# Controller.net
KiCad netlist of a schematic drawn in EAGLE
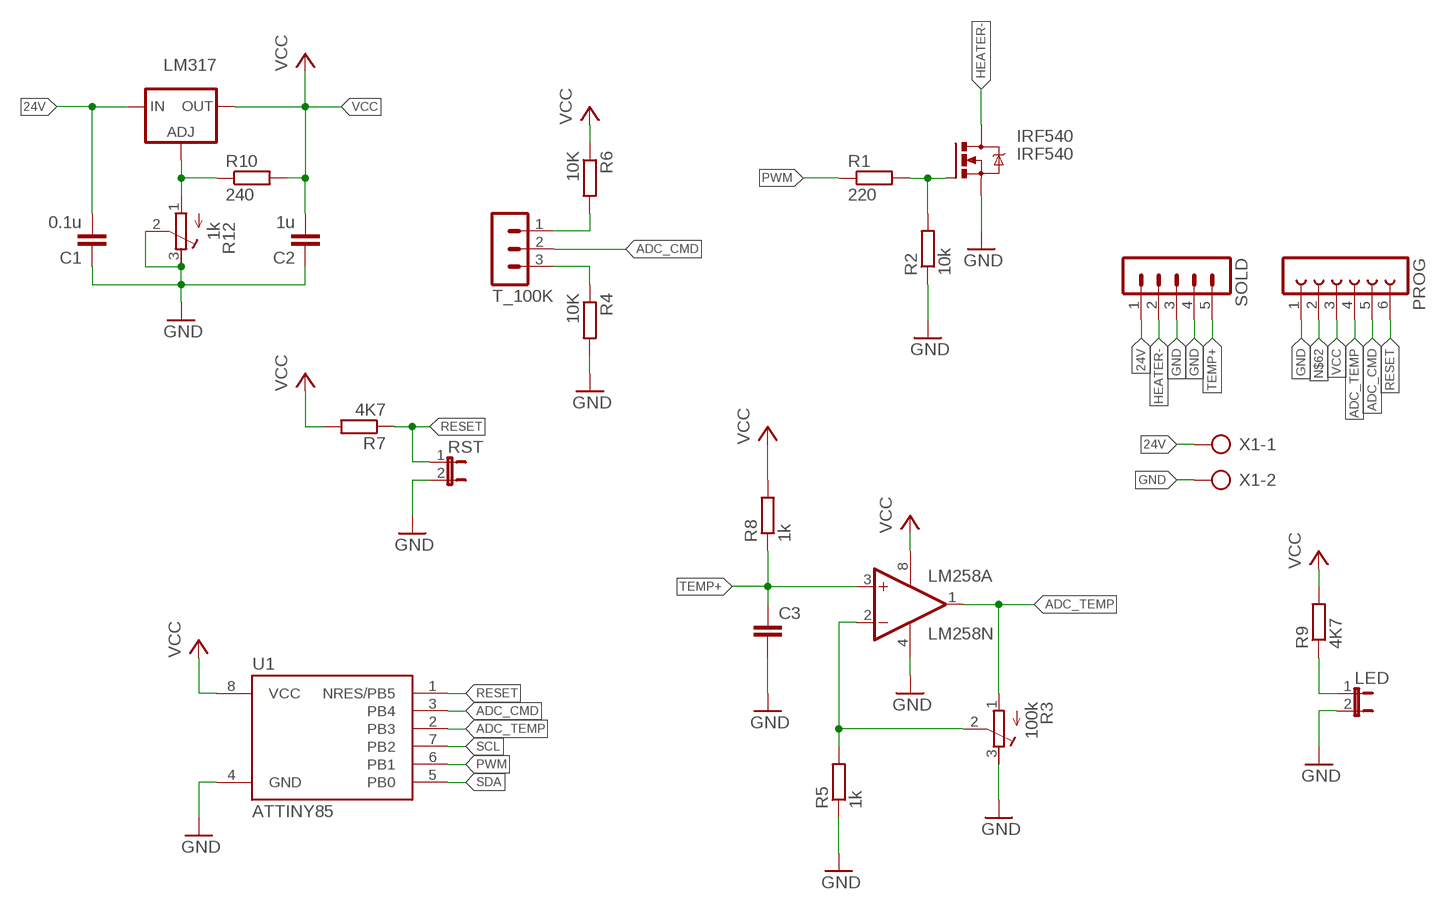
[diagram p0: schematic, sheet 1]

(export (version "E")
  (design (tool "Eeschema 10.0.6"))
  (components
    (comp (ref "C1")
      (value "0.1u")
      (footprint "eagle-import:C025-025X050")
      (libsource (lib "eagle-import") (part "C-EU025-025X050"))
    )
    (comp (ref "C2")
      (value "1u")
      (footprint "eagle-import:C025-025X050")
      (libsource (lib "eagle-import") (part "C-EU025-025X050"))
    )
    (comp (ref "C3")
      (value "C-EU025-025X050")
      (footprint "eagle-import:C025-025X050")
      (libsource (lib "eagle-import") (part "C-EU025-025X050"))
    )
    (comp (ref "IRF540")
      (value "IRF540")
      (footprint "eagle-import:TO220BV")
      (libsource (lib "eagle-import") (part "IRF540"))
    )
    (comp (ref "LED")
      (value "JP1E")
      (footprint "eagle-import:JP1")
      (libsource (lib "eagle-import") (part "JP1E"))
    )
    (comp (ref "LM258")
      (value "LM258N")
      (footprint "eagle-import:DIL08")
      (libsource (lib "eagle-import") (part "LM2903N"))
    )
    (comp (ref "LM317")
      (value "LM317TS")
      (footprint "eagle-import:317TS")
      (libsource (lib "eagle-import") (part "LM317TS"))
    )
    (comp (ref "PROG")
      (value "FE06-1")
      (footprint "eagle-import:FE06")
      (libsource (lib "eagle-import") (part "FE06-1"))
    )
    (comp (ref "R1")
      (value "220")
      (footprint "eagle-import:0204_7")
      (libsource (lib "eagle-import") (part "R-EU_0204/7"))
    )
    (comp (ref "R2")
      (value "10k")
      (footprint "eagle-import:0204_7")
      (libsource (lib "eagle-import") (part "R-EU_0204/7"))
    )
    (comp (ref "R3")
      (value "100k")
      (footprint "eagle-import:RTRIM64W")
      (libsource (lib "eagle-import") (part "R-TRIMM64W"))
    )
    (comp (ref "R4")
      (value "10K")
      (footprint "eagle-import:0204V")
      (libsource (lib "eagle-import") (part "R-EU_0204/2V"))
    )
    (comp (ref "R5")
      (value "1k")
      (footprint "eagle-import:0204_7")
      (libsource (lib "eagle-import") (part "R-EU_0204/7"))
    )
    (comp (ref "R6")
      (value "10K")
      (footprint "eagle-import:0204_7")
      (libsource (lib "eagle-import") (part "R-EU_0204/7"))
    )
    (comp (ref "R7")
      (value "4K7")
      (footprint "eagle-import:0204_7")
      (libsource (lib "eagle-import") (part "R-EU_0204/7"))
    )
    (comp (ref "R8")
      (value "1k")
      (footprint "eagle-import:0204_7")
      (libsource (lib "eagle-import") (part "R-EU_0204/7"))
    )
    (comp (ref "R9")
      (value "4K7")
      (footprint "eagle-import:0204_7")
      (libsource (lib "eagle-import") (part "R-EU_0204/7"))
    )
    (comp (ref "R10")
      (value "240")
      (footprint "eagle-import:0204_7")
      (libsource (lib "eagle-import") (part "R-EU_0204/7"))
    )
    (comp (ref "R12")
      (value "1k")
      (footprint "eagle-import:RTRIM64W")
      (libsource (lib "eagle-import") (part "R-TRIMM64W"))
    )
    (comp (ref "RST")
      (value "JP1E")
      (footprint "eagle-import:JP1")
      (libsource (lib "eagle-import") (part "JP1E"))
    )
    (comp (ref "SOLD")
      (value "MA05-1")
      (footprint "eagle-import:MA05-1")
      (libsource (lib "eagle-import") (part "MA05-1"))
    )
    (comp (ref "T_100K")
      (value "MA03-1")
      (footprint "eagle-import:MA03-1")
      (libsource (lib "eagle-import") (part "MA03-1"))
    )
    (comp (ref "U1")
      (value "ATTINY85")
      (footprint "eagle-import:PDIP08_300MIL")
      (libsource (lib "eagle-import") (part "ATTINY85P-"))
    )
    (comp (ref "X1")
      (value "SMKDSP_1,5/2")
      (footprint "eagle-import:SMKDSP_1,5_2")
      (fields (field (name "MF") "FARNELL") (field (name "MPN") "1733570"))
      (libsource (lib "eagle-import") (part "SMKDSP_1,5/2"))
    )
  )
  (nets
    (net (code "1") (name "24V") (class "Default")
      (node (ref "C1") (pin "2") (pinfunction "2_2") (pintype "passive"))
      (node (ref "LM317") (pin "3") (pinfunction "IN_3") (pintype "input"))
      (node (ref "SOLD") (pin "1") (pinfunction "1_1") (pintype "passive"))
      (node (ref "X1") (pin "1") (pinfunction "KL_1") (pintype "passive"))
    )
    (net (code "2") (name "ADC_CMD") (class "Default")
      (node (ref "PROG") (pin "5") (pinfunction "5_5") (pintype "passive"))
      (node (ref "R6") (pin "2") (pinfunction "2_2") (pintype "passive"))
      (node (ref "T_100K") (pin "1") (pinfunction "1_1") (pintype "passive"))
      (node (ref "T_100K") (pin "2") (pinfunction "2_2") (pintype "passive"))
      (node (ref "U1") (pin "3") (pinfunction "PB4_3") (pintype "bidirectional"))
    )
    (net (code "3") (name "ADC_TEMP") (class "Default")
      (node (ref "LM258") (pin "1") (pinfunction "OUT_1") (pintype "output"))
      (node (ref "PROG") (pin "4") (pinfunction "4_4") (pintype "passive"))
      (node (ref "R3") (pin "1") (pinfunction "A_1") (pintype "passive"))
      (node (ref "U1") (pin "2") (pinfunction "PB3_2") (pintype "bidirectional"))
    )
    (net (code "4") (name "GND") (class "Default")
      (node (ref "C1") (pin "1") (pinfunction "1_1") (pintype "passive"))
      (node (ref "C2") (pin "1") (pinfunction "1_1") (pintype "passive"))
      (node (ref "C3") (pin "2") (pinfunction "2_2") (pintype "passive"))
      (node (ref "IRF540") (pin "S") (pinfunction "S_S") (pintype "passive"))
      (node (ref "LED") (pin "2") (pinfunction "2_2") (pintype "passive"))
      (node (ref "LM258") (pin "4") (pinfunction "V-_4") (pintype "power_in"))
      (node (ref "PROG") (pin "1") (pinfunction "1_1") (pintype "passive"))
      (node (ref "R12") (pin "2") (pinfunction "S_2") (pintype "passive"))
      (node (ref "R12") (pin "3") (pinfunction "E_3") (pintype "passive"))
      (node (ref "R2") (pin "1") (pinfunction "1_1") (pintype "passive"))
      (node (ref "R3") (pin "3") (pinfunction "E_3") (pintype "passive"))
      (node (ref "R4") (pin "2") (pinfunction "2_2") (pintype "passive"))
      (node (ref "R5") (pin "1") (pinfunction "1_1") (pintype "passive"))
      (node (ref "RST") (pin "2") (pinfunction "2_2") (pintype "passive"))
      (node (ref "SOLD") (pin "3") (pinfunction "3_3") (pintype "passive"))
      (node (ref "SOLD") (pin "4") (pinfunction "4_4") (pintype "passive"))
      (node (ref "U1") (pin "4") (pinfunction "GND_4") (pintype "power_in"))
      (node (ref "X1") (pin "2") (pinfunction "KL_2") (pintype "passive"))
    )
    (net (code "5") (name "HEATER-") (class "Default")
      (node (ref "IRF540") (pin "D") (pinfunction "D_D") (pintype "passive"))
      (node (ref "SOLD") (pin "2") (pinfunction "2_2") (pintype "passive"))
    )
    (net (code "6") (name "N$62") (class "Default")
      (node (ref "PROG") (pin "2") (pinfunction "2_2") (pintype "passive"))
    )
    (net (code "7") (name "Net-(IRF540-PadG)") (class "Default")
      (node (ref "IRF540") (pin "G") (pinfunction "G_G") (pintype "passive"))
      (node (ref "R1") (pin "2") (pinfunction "2_2") (pintype "passive"))
      (node (ref "R2") (pin "2") (pinfunction "2_2") (pintype "passive"))
    )
    (net (code "8") (name "Net-(LED-Pad1)") (class "Default")
      (node (ref "LED") (pin "1") (pinfunction "1_1") (pintype "passive"))
      (node (ref "R9") (pin "1") (pinfunction "1_1") (pintype "passive"))
    )
    (net (code "9") (name "Net-(LM258A--IN)") (class "Default")
      (node (ref "LM258") (pin "2") (pinfunction "-IN_2") (pintype "input"))
      (node (ref "R3") (pin "2") (pinfunction "S_2") (pintype "passive"))
      (node (ref "R5") (pin "2") (pinfunction "2_2") (pintype "passive"))
    )
    (net (code "10") (name "Net-(LM317-ADJ)") (class "Default")
      (node (ref "LM317") (pin "1") (pinfunction "ADJ_1") (pintype "input"))
      (node (ref "R10") (pin "1") (pinfunction "1_1") (pintype "passive"))
      (node (ref "R12") (pin "1") (pinfunction "A_1") (pintype "passive"))
    )
    (net (code "11") (name "Net-(R4-Pad1)") (class "Default")
      (node (ref "R4") (pin "1") (pinfunction "1_1") (pintype "passive"))
      (node (ref "T_100K") (pin "3") (pinfunction "3_3") (pintype "passive"))
    )
    (net (code "12") (name "PWM") (class "Default")
      (node (ref "R1") (pin "1") (pinfunction "1_1") (pintype "passive"))
      (node (ref "U1") (pin "6") (pinfunction "PB1_6") (pintype "bidirectional"))
    )
    (net (code "13") (name "RESET") (class "Default")
      (node (ref "PROG") (pin "6") (pinfunction "6_6") (pintype "passive"))
      (node (ref "R7") (pin "1") (pinfunction "1_1") (pintype "passive"))
      (node (ref "RST") (pin "1") (pinfunction "1_1") (pintype "passive"))
      (node (ref "U1") (pin "1") (pinfunction "NRES/PB5_1") (pintype "bidirectional"))
    )
    (net (code "14") (name "SCL") (class "Default")
      (node (ref "U1") (pin "7") (pinfunction "PB2_7") (pintype "bidirectional"))
    )
    (net (code "15") (name "SDA") (class "Default")
      (node (ref "U1") (pin "5") (pinfunction "PB0_5") (pintype "bidirectional"))
    )
    (net (code "16") (name "TEMP+") (class "Default")
      (node (ref "C3") (pin "1") (pinfunction "1_1") (pintype "passive"))
      (node (ref "LM258") (pin "3") (pinfunction "+IN_3") (pintype "input"))
      (node (ref "R8") (pin "1") (pinfunction "1_1") (pintype "passive"))
      (node (ref "SOLD") (pin "5") (pinfunction "5_5") (pintype "passive"))
    )
    (net (code "17") (name "VCC") (class "Default")
      (node (ref "C2") (pin "2") (pinfunction "2_2") (pintype "passive"))
      (node (ref "LM258") (pin "8") (pinfunction "V+_8") (pintype "power_in"))
      (node (ref "LM317") (pin "2") (pinfunction "OUT_2") (pintype "passive"))
      (node (ref "PROG") (pin "3") (pinfunction "3_3") (pintype "passive"))
      (node (ref "R10") (pin "2") (pinfunction "2_2") (pintype "passive"))
      (node (ref "R6") (pin "1") (pinfunction "1_1") (pintype "passive"))
      (node (ref "R7") (pin "2") (pinfunction "2_2") (pintype "passive"))
      (node (ref "R8") (pin "2") (pinfunction "2_2") (pintype "passive"))
      (node (ref "R9") (pin "2") (pinfunction "2_2") (pintype "passive"))
      (node (ref "U1") (pin "8") (pinfunction "VCC_8") (pintype "power_in"))
    )
  )
)
